# pcb.net
KiCad netlist of a schematic drawn in EAGLE
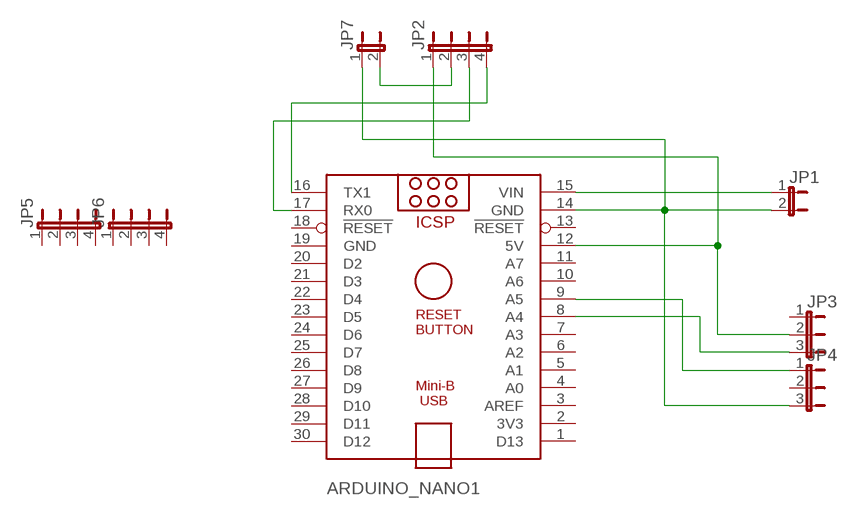
[diagram p0: schematic, sheet 1]

(export (version "E")
  (design (tool "Eeschema 10.0.6"))
  (components
    (comp (ref "ARDUINO_NANO1")
      (value "ARDUINO_NANO")
      (footprint "eagle-import:ARDUINO_NANO")
      (libsource (lib "eagle-import") (part "ARDUINO_NANO"))
    )
    (comp (ref "JP1")
      (value "JP1E")
      (footprint "eagle-import:JP1")
      (libsource (lib "eagle-import") (part "JP1E"))
    )
    (comp (ref "JP2")
      (value "JP4E")
      (footprint "eagle-import:JP4")
      (libsource (lib "eagle-import") (part "JP4E"))
    )
    (comp (ref "JP3")
      (value "JP2E")
      (footprint "eagle-import:JP2")
      (libsource (lib "eagle-import") (part "JP2E"))
    )
    (comp (ref "JP4")
      (value "JP2E")
      (footprint "eagle-import:JP2")
      (libsource (lib "eagle-import") (part "JP2E"))
    )
    (comp (ref "JP5")
      (value "JP4E")
      (footprint "eagle-import:JP4")
      (libsource (lib "eagle-import") (part "JP4E"))
    )
    (comp (ref "JP6")
      (value "JP4E")
      (footprint "eagle-import:JP4")
      (libsource (lib "eagle-import") (part "JP4E"))
    )
    (comp (ref "JP7")
      (value "JP1E")
      (footprint "eagle-import:JP1")
      (libsource (lib "eagle-import") (part "JP1E"))
    )
  )
  (nets
    (net (code "1") (name "/GND") (class "Default")
      (node (ref "ARDUINO_NANO1") (pin "19") (pinfunction "GND_19") (pintype "power_in"))
    )
    (net (code "2") (name "Net-(ARDUINO_NANO1-5V)") (class "Default")
      (node (ref "ARDUINO_NANO1") (pin "12") (pinfunction "5V_12") (pintype "power_in"))
      (node (ref "JP2") (pin "1") (pinfunction "1_1") (pintype "passive"))
      (node (ref "JP3") (pin "2") (pinfunction "2_2") (pintype "passive"))
    )
    (net (code "3") (name "Net-(ARDUINO_NANO1-A4)") (class "Default")
      (node (ref "ARDUINO_NANO1") (pin "8") (pinfunction "A4_8") (pintype "bidirectional"))
      (node (ref "JP3") (pin "3") (pinfunction "3_3") (pintype "passive"))
    )
    (net (code "4") (name "Net-(ARDUINO_NANO1-A5)") (class "Default")
      (node (ref "ARDUINO_NANO1") (pin "9") (pinfunction "A5_9") (pintype "bidirectional"))
      (node (ref "JP4") (pin "1") (pinfunction "1_1") (pintype "passive"))
    )
    (net (code "5") (name "Net-(ARDUINO_NANO1-GND-Pad14)") (class "Default")
      (node (ref "ARDUINO_NANO1") (pin "14") (pinfunction "GND_14") (pintype "power_in"))
      (node (ref "JP1") (pin "2") (pinfunction "2_2") (pintype "passive"))
      (node (ref "JP4") (pin "3") (pinfunction "3_3") (pintype "passive"))
      (node (ref "JP7") (pin "1") (pinfunction "1_1") (pintype "passive"))
    )
    (net (code "6") (name "Net-(ARDUINO_NANO1-RX0)") (class "Default")
      (node (ref "ARDUINO_NANO1") (pin "17") (pinfunction "RX0_17") (pintype "bidirectional"))
      (node (ref "JP2") (pin "3") (pinfunction "3_3") (pintype "passive"))
    )
    (net (code "7") (name "Net-(ARDUINO_NANO1-TX1)") (class "Default")
      (node (ref "ARDUINO_NANO1") (pin "16") (pinfunction "TX1_16") (pintype "bidirectional"))
      (node (ref "JP2") (pin "4") (pinfunction "4_4") (pintype "passive"))
    )
    (net (code "8") (name "Net-(ARDUINO_NANO1-VIN)") (class "Default")
      (node (ref "ARDUINO_NANO1") (pin "15") (pinfunction "VIN_15") (pintype "power_in"))
      (node (ref "JP1") (pin "1") (pinfunction "1_1") (pintype "passive"))
    )
    (net (code "9") (name "Net-(JP2-Pad2)") (class "Default")
      (node (ref "JP2") (pin "2") (pinfunction "2_2") (pintype "passive"))
      (node (ref "JP7") (pin "2") (pinfunction "2_2") (pintype "passive"))
    )
    (net (code "10") (name "unconnected-(ARDUINO_NANO1-3V3-Pad2)") (class "Default")
      (node (ref "ARDUINO_NANO1") (pin "2") (pinfunction "3V3_2") (pintype "output"))
    )
    (net (code "11") (name "unconnected-(ARDUINO_NANO1-A0-Pad4)") (class "Default")
      (node (ref "ARDUINO_NANO1") (pin "4") (pinfunction "A0_4") (pintype "bidirectional"))
    )
    (net (code "12") (name "unconnected-(ARDUINO_NANO1-A1-Pad5)") (class "Default")
      (node (ref "ARDUINO_NANO1") (pin "5") (pinfunction "A1_5") (pintype "bidirectional"))
    )
    (net (code "13") (name "unconnected-(ARDUINO_NANO1-A2-Pad6)") (class "Default")
      (node (ref "ARDUINO_NANO1") (pin "6") (pinfunction "A2_6") (pintype "bidirectional"))
    )
    (net (code "14") (name "unconnected-(ARDUINO_NANO1-A3-Pad7)") (class "Default")
      (node (ref "ARDUINO_NANO1") (pin "7") (pinfunction "A3_7") (pintype "bidirectional"))
    )
    (net (code "15") (name "unconnected-(ARDUINO_NANO1-A6-Pad10)") (class "Default")
      (node (ref "ARDUINO_NANO1") (pin "10") (pinfunction "A6_10") (pintype "bidirectional"))
    )
    (net (code "16") (name "unconnected-(ARDUINO_NANO1-A7-Pad11)") (class "Default")
      (node (ref "ARDUINO_NANO1") (pin "11") (pinfunction "A7_11") (pintype "bidirectional"))
    )
    (net (code "17") (name "unconnected-(ARDUINO_NANO1-AREF-Pad3)") (class "Default")
      (node (ref "ARDUINO_NANO1") (pin "3") (pinfunction "AREF_3") (pintype "input"))
    )
    (net (code "18") (name "unconnected-(ARDUINO_NANO1-D2-Pad20)") (class "Default")
      (node (ref "ARDUINO_NANO1") (pin "20") (pinfunction "D2_20") (pintype "bidirectional"))
    )
    (net (code "19") (name "unconnected-(ARDUINO_NANO1-D3-Pad21)") (class "Default")
      (node (ref "ARDUINO_NANO1") (pin "21") (pinfunction "D3_21") (pintype "bidirectional"))
    )
    (net (code "20") (name "unconnected-(ARDUINO_NANO1-D4-Pad22)") (class "Default")
      (node (ref "ARDUINO_NANO1") (pin "22") (pinfunction "D4_22") (pintype "bidirectional"))
    )
    (net (code "21") (name "unconnected-(ARDUINO_NANO1-D5-Pad23)") (class "Default")
      (node (ref "ARDUINO_NANO1") (pin "23") (pinfunction "D5_23") (pintype "bidirectional"))
    )
    (net (code "22") (name "unconnected-(ARDUINO_NANO1-D6-Pad24)") (class "Default")
      (node (ref "ARDUINO_NANO1") (pin "24") (pinfunction "D6_24") (pintype "bidirectional"))
    )
    (net (code "23") (name "unconnected-(ARDUINO_NANO1-D7-Pad25)") (class "Default")
      (node (ref "ARDUINO_NANO1") (pin "25") (pinfunction "D7_25") (pintype "bidirectional"))
    )
    (net (code "24") (name "unconnected-(ARDUINO_NANO1-D8-Pad26)") (class "Default")
      (node (ref "ARDUINO_NANO1") (pin "26") (pinfunction "D8_26") (pintype "bidirectional"))
    )
    (net (code "25") (name "unconnected-(ARDUINO_NANO1-D9-Pad27)") (class "Default")
      (node (ref "ARDUINO_NANO1") (pin "27") (pinfunction "D9_27") (pintype "bidirectional"))
    )
    (net (code "26") (name "unconnected-(ARDUINO_NANO1-D10-Pad28)") (class "Default")
      (node (ref "ARDUINO_NANO1") (pin "28") (pinfunction "D10_28") (pintype "bidirectional"))
    )
    (net (code "27") (name "unconnected-(ARDUINO_NANO1-D11-Pad29)") (class "Default")
      (node (ref "ARDUINO_NANO1") (pin "29") (pinfunction "D11_29") (pintype "bidirectional"))
    )
    (net (code "28") (name "unconnected-(ARDUINO_NANO1-D12-Pad30)") (class "Default")
      (node (ref "ARDUINO_NANO1") (pin "30") (pinfunction "D12_30") (pintype "bidirectional"))
    )
    (net (code "29") (name "unconnected-(ARDUINO_NANO1-D13-Pad1)") (class "Default")
      (node (ref "ARDUINO_NANO1") (pin "1") (pinfunction "D13_1") (pintype "bidirectional"))
    )
    (net (code "30") (name "unconnected-(ARDUINO_NANO1-~{RESET}-Pad13)") (class "Default")
      (node (ref "ARDUINO_NANO1") (pin "13") (pinfunction "~{RESET}_13") (pintype "input"))
    )
    (net (code "31") (name "unconnected-(ARDUINO_NANO1-~{RESET}-Pad18)") (class "Default")
      (node (ref "ARDUINO_NANO1") (pin "18") (pinfunction "~{RESET}_18") (pintype "input"))
    )
    (net (code "32") (name "unconnected-(JP3-Pad1)") (class "Default")
      (node (ref "JP3") (pin "1") (pinfunction "1_1") (pintype "passive"))
    )
    (net (code "33") (name "unconnected-(JP4-Pad2)") (class "Default")
      (node (ref "JP4") (pin "2") (pinfunction "2_2") (pintype "passive"))
    )
    (net (code "34") (name "unconnected-(JP5-Pad1)") (class "Default")
      (node (ref "JP5") (pin "1") (pinfunction "1_1") (pintype "passive"))
    )
    (net (code "35") (name "unconnected-(JP5-Pad2)") (class "Default")
      (node (ref "JP5") (pin "2") (pinfunction "2_2") (pintype "passive"))
    )
    (net (code "36") (name "unconnected-(JP5-Pad3)") (class "Default")
      (node (ref "JP5") (pin "3") (pinfunction "3_3") (pintype "passive"))
    )
    (net (code "37") (name "unconnected-(JP5-Pad4)") (class "Default")
      (node (ref "JP5") (pin "4") (pinfunction "4_4") (pintype "passive"))
    )
    (net (code "38") (name "unconnected-(JP6-Pad1)") (class "Default")
      (node (ref "JP6") (pin "1") (pinfunction "1_1") (pintype "passive"))
    )
    (net (code "39") (name "unconnected-(JP6-Pad2)") (class "Default")
      (node (ref "JP6") (pin "2") (pinfunction "2_2") (pintype "passive"))
    )
    (net (code "40") (name "unconnected-(JP6-Pad3)") (class "Default")
      (node (ref "JP6") (pin "3") (pinfunction "3_3") (pintype "passive"))
    )
    (net (code "41") (name "unconnected-(JP6-Pad4)") (class "Default")
      (node (ref "JP6") (pin "4") (pinfunction "4_4") (pintype "passive"))
    )
  )
)
